# DB.net
KiCad netlist of a schematic drawn in Altium Designer
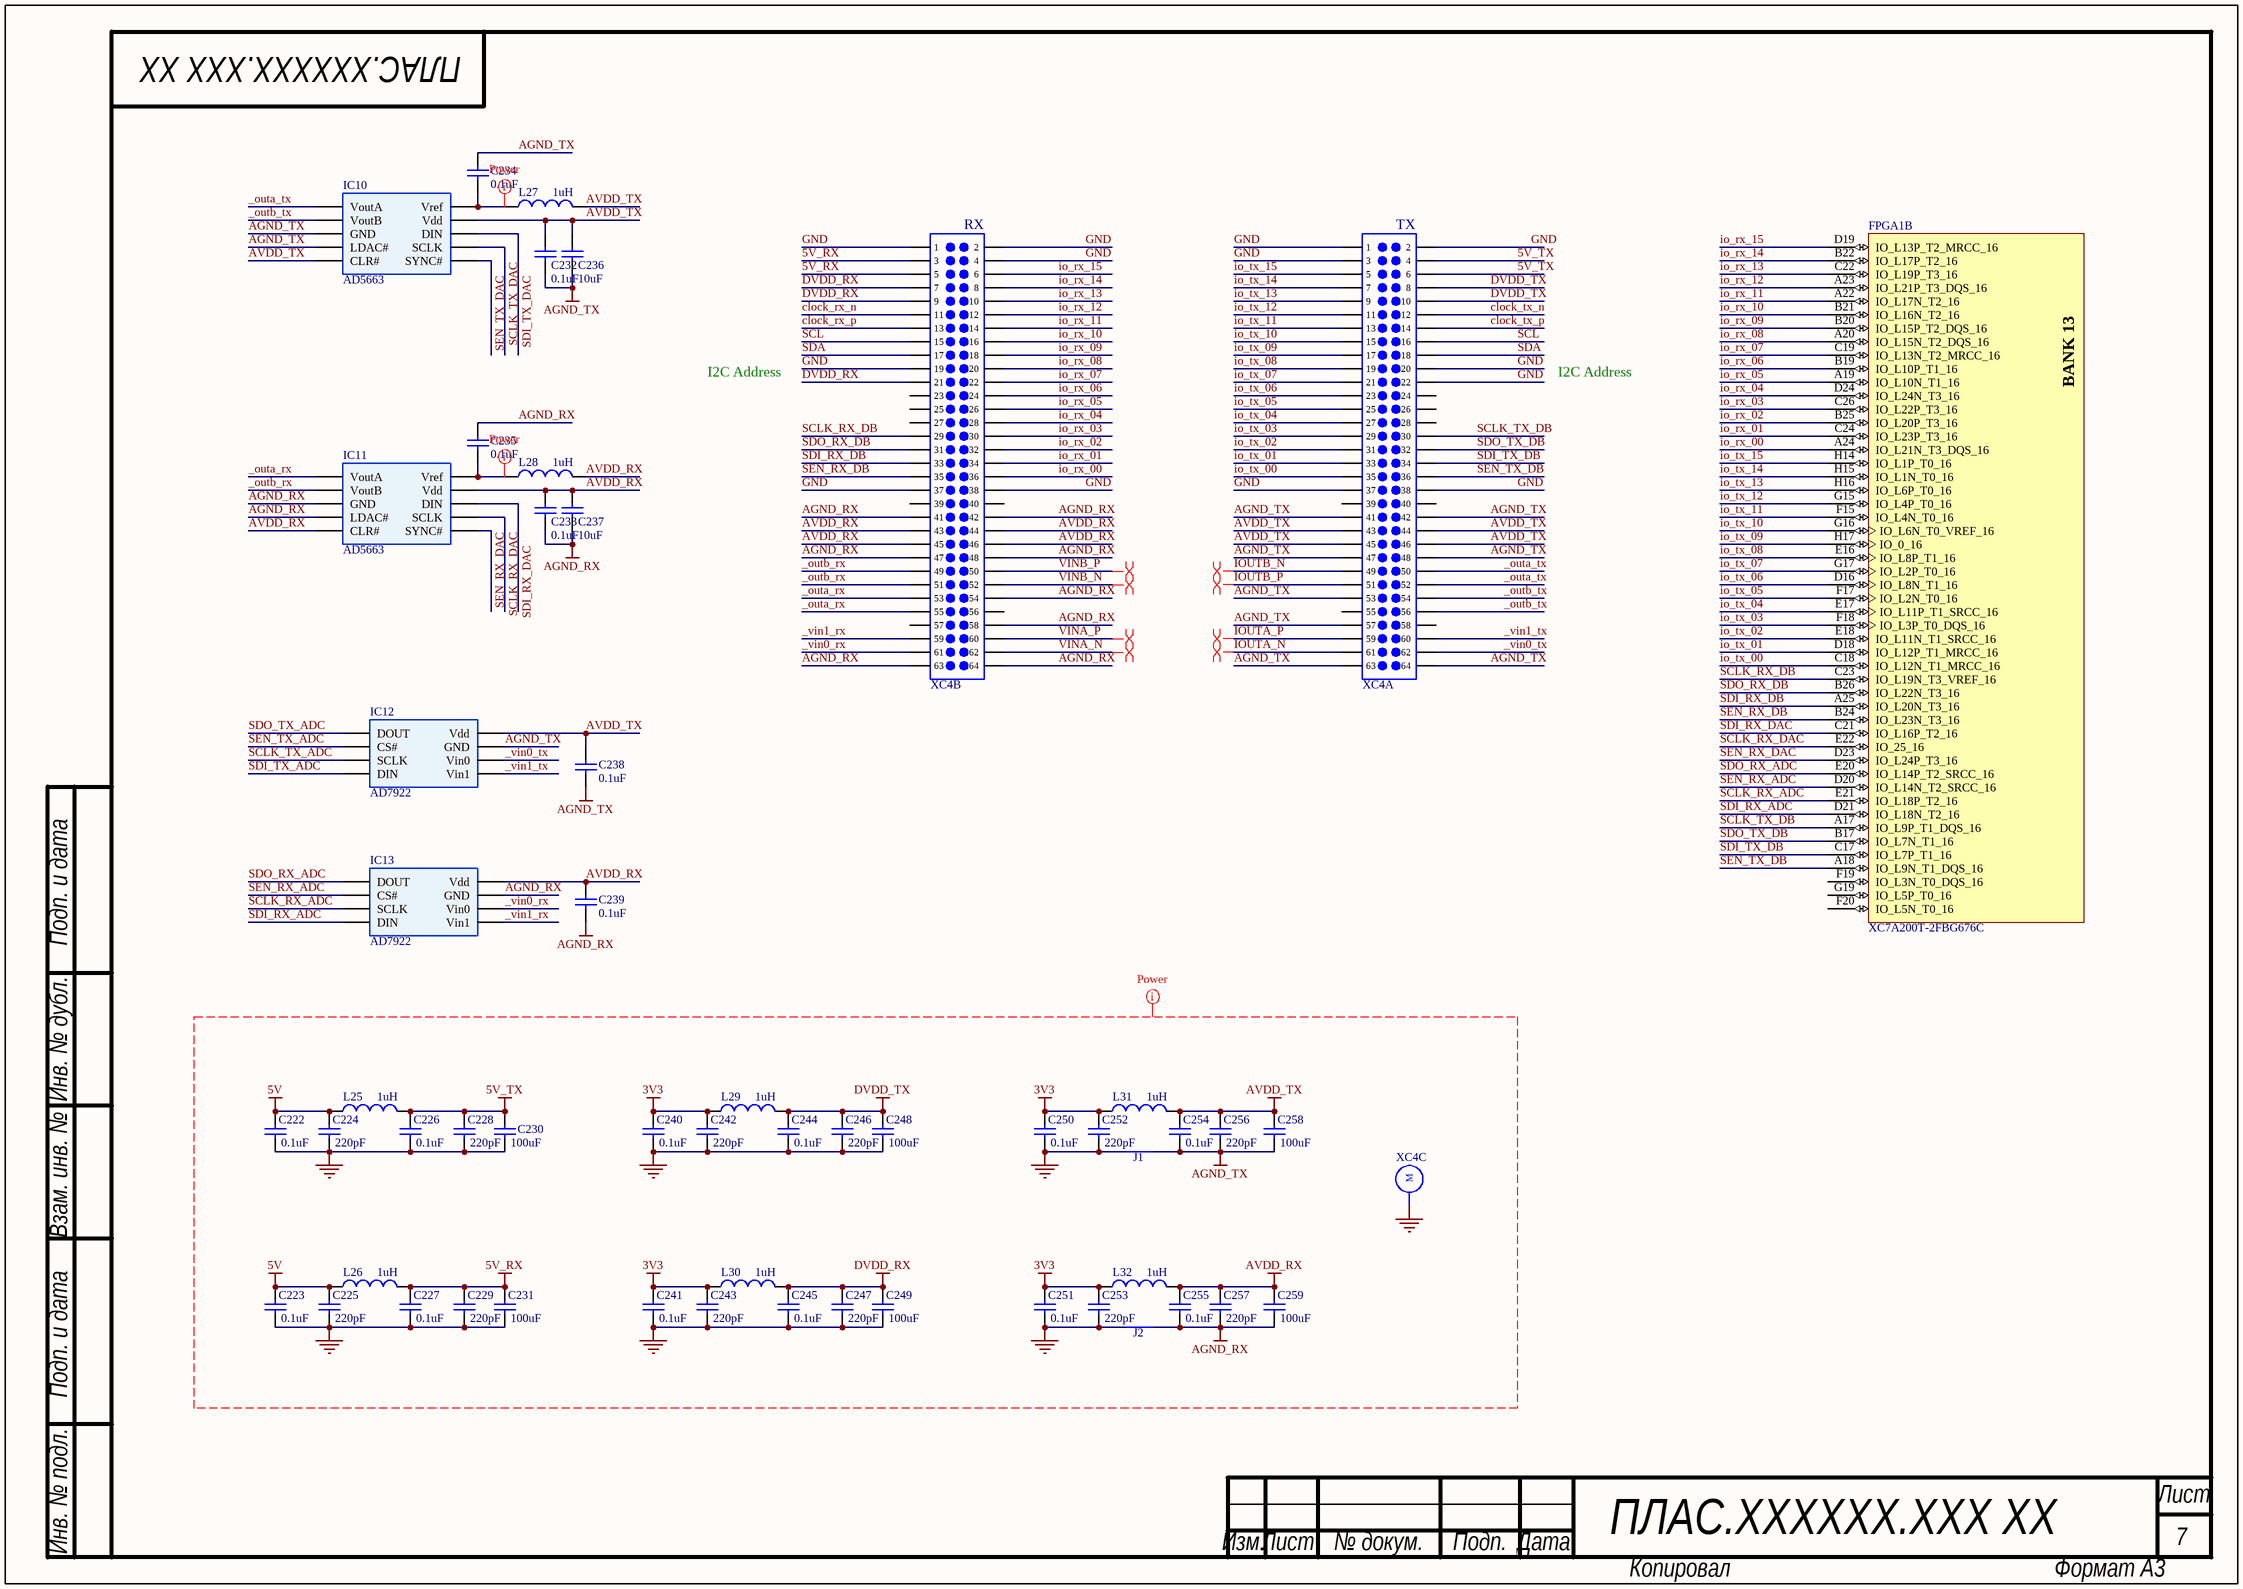
[diagram p0: DB.SchDoc]

(export (version "E")
  (design (tool "Eeschema 10.0.6"))
  (components
    (comp (ref "C222")
      (value "0.1uF")
      (footprint "C0603")
      (description "Cer Cap Small")
      (fields (field (name "MANUFACTURER") "Murata") (field (name "VOLTAGE") "16V"))
      (libsource (lib "USRP2_Clone") (part "Cer Cap"))
    )
    (comp (ref "C223")
      (value "0.1uF")
      (footprint "C0603")
      (description "Cer Cap Small")
      (fields (field (name "MANUFACTURER") "Murata") (field (name "VOLTAGE") "16V"))
      (libsource (lib "USRP2_Clone") (part "Cer Cap"))
    )
    (comp (ref "C224")
      (value "220pF")
      (footprint "C0603")
      (description "Cer Cap Small")
      (fields (field (name "MANUFACTURER") "Murata") (field (name "VOLTAGE") "16V"))
      (libsource (lib "USRP2_Clone") (part "Cer Cap"))
    )
    (comp (ref "C225")
      (value "220pF")
      (footprint "C0603")
      (description "Cer Cap Small")
      (fields (field (name "MANUFACTURER") "Murata") (field (name "VOLTAGE") "16V"))
      (libsource (lib "USRP2_Clone") (part "Cer Cap"))
    )
    (comp (ref "C226")
      (value "0.1uF")
      (footprint "C0603")
      (description "Cer Cap Small")
      (fields (field (name "MANUFACTURER") "Murata") (field (name "VOLTAGE") "16V"))
      (libsource (lib "USRP2_Clone") (part "Cer Cap"))
    )
    (comp (ref "C227")
      (value "0.1uF")
      (footprint "C0603")
      (description "Cer Cap Small")
      (fields (field (name "MANUFACTURER") "Murata") (field (name "VOLTAGE") "16V"))
      (libsource (lib "USRP2_Clone") (part "Cer Cap"))
    )
    (comp (ref "C228")
      (value "220pF")
      (footprint "C0603")
      (description "Cer Cap Small")
      (fields (field (name "MANUFACTURER") "Murata") (field (name "VOLTAGE") "16V"))
      (libsource (lib "USRP2_Clone") (part "Cer Cap"))
    )
    (comp (ref "C229")
      (value "220pF")
      (footprint "C0603")
      (description "Cer Cap Small")
      (fields (field (name "MANUFACTURER") "Murata") (field (name "VOLTAGE") "16V"))
      (libsource (lib "USRP2_Clone") (part "Cer Cap"))
    )
    (comp (ref "C230")
      (value "100uF")
      (footprint "C1210")
      (description "Cer Cap Large")
      (fields (field (name "MANUFACTURER") "Murata") (field (name "TOLERANCE") "20%"))
      (libsource (lib "USRP2_Clone") (part "Cap uF"))
    )
    (comp (ref "C231")
      (value "100uF")
      (footprint "C1210")
      (description "Cer Cap Large")
      (fields (field (name "MANUFACTURER") "Murata") (field (name "TOLERANCE") "20%"))
      (libsource (lib "USRP2_Clone") (part "Cap uF"))
    )
    (comp (ref "C232")
      (value "0.1uF")
      (footprint "C0603")
      (description "Cer Cap Small")
      (fields (field (name "MANUFACTURER") "Murata") (field (name "VOLTAGE") "16V"))
      (libsource (lib "USRP2_Clone") (part "Cer Cap"))
    )
    (comp (ref "C233")
      (value "0.1uF")
      (footprint "C0603")
      (description "Cer Cap Small")
      (fields (field (name "MANUFACTURER") "Murata") (field (name "VOLTAGE") "16V"))
      (libsource (lib "USRP2_Clone") (part "Cer Cap"))
    )
    (comp (ref "C234")
      (value "0.1uF")
      (footprint "C0603")
      (description "Cer Cap Small")
      (fields (field (name "MANUFACTURER") "Murata") (field (name "VOLTAGE") "16V"))
      (libsource (lib "USRP2_Clone") (part "Cer Cap"))
    )
    (comp (ref "C235")
      (value "0.1uF")
      (footprint "C0603")
      (description "Cer Cap Small")
      (fields (field (name "MANUFACTURER") "Murata") (field (name "VOLTAGE") "16V"))
      (libsource (lib "USRP2_Clone") (part "Cer Cap"))
    )
    (comp (ref "C236")
      (value "10uF")
      (footprint "C0603")
      (description "Cer Cap Small")
      (fields (field (name "MANUFACTURER") "Murata") (field (name "VOLTAGE") "6.3V"))
      (libsource (lib "USRP2_Clone") (part "Cer Cap"))
    )
    (comp (ref "C237")
      (value "10uF")
      (footprint "C0603")
      (description "Cer Cap Small")
      (fields (field (name "MANUFACTURER") "Murata") (field (name "VOLTAGE") "6.3V"))
      (libsource (lib "USRP2_Clone") (part "Cer Cap"))
    )
    (comp (ref "C238")
      (value "0.1uF")
      (footprint "C0603")
      (description "Cer Cap Small")
      (fields (field (name "MANUFACTURER") "Murata") (field (name "VOLTAGE") "16V"))
      (libsource (lib "") (part "Cer Cap_1"))
    )
    (comp (ref "C239")
      (value "0.1uF")
      (footprint "C0603")
      (description "Cer Cap Small")
      (fields (field (name "MANUFACTURER") "Murata") (field (name "VOLTAGE") "16V"))
      (libsource (lib "USRP2_Clone") (part "Cer Cap"))
    )
    (comp (ref "C240")
      (value "0.1uF")
      (footprint "C0603")
      (description "Cer Cap Small")
      (fields (field (name "MANUFACTURER") "Murata") (field (name "VOLTAGE") "16V"))
      (libsource (lib "USRP2_Clone") (part "Cer Cap"))
    )
    (comp (ref "C241")
      (value "0.1uF")
      (footprint "C0603")
      (description "Cer Cap Small")
      (fields (field (name "MANUFACTURER") "Murata") (field (name "VOLTAGE") "16V"))
      (libsource (lib "USRP2_Clone") (part "Cer Cap"))
    )
    (comp (ref "C242")
      (value "220pF")
      (footprint "C0603")
      (description "Cer Cap Small")
      (fields (field (name "MANUFACTURER") "Murata") (field (name "VOLTAGE") "16V"))
      (libsource (lib "USRP2_Clone") (part "Cer Cap"))
    )
    (comp (ref "C243")
      (value "220pF")
      (footprint "C0603")
      (description "Cer Cap Small")
      (fields (field (name "MANUFACTURER") "Murata") (field (name "VOLTAGE") "16V"))
      (libsource (lib "USRP2_Clone") (part "Cer Cap"))
    )
    (comp (ref "C244")
      (value "0.1uF")
      (footprint "C0603")
      (description "Cer Cap Small")
      (fields (field (name "MANUFACTURER") "Murata") (field (name "VOLTAGE") "16V"))
      (libsource (lib "USRP2_Clone") (part "Cer Cap"))
    )
    (comp (ref "C245")
      (value "0.1uF")
      (footprint "C0603")
      (description "Cer Cap Small")
      (fields (field (name "MANUFACTURER") "Murata") (field (name "VOLTAGE") "16V"))
      (libsource (lib "USRP2_Clone") (part "Cer Cap"))
    )
    (comp (ref "C246")
      (value "220pF")
      (footprint "C0603")
      (description "Cer Cap Small")
      (fields (field (name "MANUFACTURER") "Murata") (field (name "VOLTAGE") "16V"))
      (libsource (lib "USRP2_Clone") (part "Cer Cap"))
    )
    (comp (ref "C247")
      (value "220pF")
      (footprint "C0603")
      (description "Cer Cap Small")
      (fields (field (name "MANUFACTURER") "Murata") (field (name "VOLTAGE") "16V"))
      (libsource (lib "USRP2_Clone") (part "Cer Cap"))
    )
    (comp (ref "C248")
      (value "100uF")
      (footprint "C1210")
      (description "Cer Cap Large")
      (fields (field (name "MANUFACTURER") "Murata") (field (name "TOLERANCE") "20%"))
      (libsource (lib "USRP2_Clone") (part "Cap uF"))
    )
    (comp (ref "C249")
      (value "100uF")
      (footprint "C1210")
      (description "Cer Cap Large")
      (fields (field (name "MANUFACTURER") "Murata") (field (name "TOLERANCE") "20%"))
      (libsource (lib "USRP2_Clone") (part "Cap uF"))
    )
    (comp (ref "C250")
      (value "0.1uF")
      (footprint "C0603")
      (description "Cer Cap Small")
      (fields (field (name "MANUFACTURER") "Murata") (field (name "VOLTAGE") "16V"))
      (libsource (lib "USRP2_Clone") (part "Cer Cap"))
    )
    (comp (ref "C251")
      (value "0.1uF")
      (footprint "C0603")
      (description "Cer Cap Small")
      (fields (field (name "MANUFACTURER") "Murata") (field (name "VOLTAGE") "16V"))
      (libsource (lib "USRP2_Clone") (part "Cer Cap"))
    )
    (comp (ref "C252")
      (value "220pF")
      (footprint "C0603")
      (description "Cer Cap Small")
      (fields (field (name "MANUFACTURER") "Murata") (field (name "VOLTAGE") "16V"))
      (libsource (lib "USRP2_Clone") (part "Cer Cap"))
    )
    (comp (ref "C253")
      (value "220pF")
      (footprint "C0603")
      (description "Cer Cap Small")
      (fields (field (name "MANUFACTURER") "Murata") (field (name "VOLTAGE") "16V"))
      (libsource (lib "USRP2_Clone") (part "Cer Cap"))
    )
    (comp (ref "C254")
      (value "0.1uF")
      (footprint "C0603")
      (description "Cer Cap Small")
      (fields (field (name "MANUFACTURER") "Murata") (field (name "VOLTAGE") "16V"))
      (libsource (lib "USRP2_Clone") (part "Cer Cap"))
    )
    (comp (ref "C255")
      (value "0.1uF")
      (footprint "C0603")
      (description "Cer Cap Small")
      (fields (field (name "MANUFACTURER") "Murata") (field (name "VOLTAGE") "16V"))
      (libsource (lib "USRP2_Clone") (part "Cer Cap"))
    )
    (comp (ref "C256")
      (value "220pF")
      (footprint "C0603")
      (description "Cer Cap Small")
      (fields (field (name "MANUFACTURER") "Murata") (field (name "VOLTAGE") "16V"))
      (libsource (lib "USRP2_Clone") (part "Cer Cap"))
    )
    (comp (ref "C257")
      (value "220pF")
      (footprint "C0603")
      (description "Cer Cap Small")
      (fields (field (name "MANUFACTURER") "Murata") (field (name "VOLTAGE") "16V"))
      (libsource (lib "USRP2_Clone") (part "Cer Cap"))
    )
    (comp (ref "C258")
      (value "100uF")
      (footprint "C1210")
      (description "Cer Cap Large")
      (fields (field (name "MANUFACTURER") "Murata") (field (name "TOLERANCE") "20%"))
      (libsource (lib "USRP2_Clone") (part "Cap uF"))
    )
    (comp (ref "C259")
      (value "100uF")
      (footprint "C1210")
      (description "Cer Cap Large")
      (fields (field (name "MANUFACTURER") "Murata") (field (name "TOLERANCE") "20%"))
      (libsource (lib "USRP2_Clone") (part "Cap uF"))
    )
    (comp (ref "FPGA1")
      (value "XC7A200T-2FBG676C")
      (footprint "FGG676")
      (description "Artix-7 FPGA, 400 User I/Os, 8 GTP, 676-Ball BGA, Speed Grade 2, Commercial Grade, Pb-Free")
      (fields (field (name "GENERIC PART NUMBER") "XC7A200T") (field (name "MANUFACTURER") "Xilinx"))
      (libsource (lib "USRP2_Clone") (part "XC7A200T-2FBG676C"))
    )
    (comp (ref "IC10")
      (value "AD5663")
      (footprint "MSOP-10")
      (description "Dual 12-/14-/16-Bit nanoDAC")
      (fields (field (name "VOLTAGE") "2.7 V to 5.5 V") (field (name "MANUFACTURER") "Analog Device"))
      (libsource (lib "USRP2_Clone") (part "AD56x3R"))
    )
    (comp (ref "IC11")
      (value "AD5663")
      (footprint "MSOP-10")
      (description "Dual 12-/14-/16-Bit nanoDAC")
      (fields (field (name "VOLTAGE") "2.7 V to 5.5 V") (field (name "MANUFACTURER") "Analog Device"))
      (libsource (lib "USRP2_Clone") (part "AD56x3R"))
    )
    (comp (ref "IC12")
      (value "AD7922")
      (footprint "MSOP-8")
      (description "1 MSPS, 10-/12-Bit ADC")
      (fields (field (name "VOLTAGE") "2.35 V to 5.25 V") (field (name "MANUFACTURER") "Analog Device"))
      (libsource (lib "USRP2_Clone") (part "AD79x2"))
    )
    (comp (ref "IC13")
      (value "AD7922")
      (footprint "MSOP-8")
      (description "1 MSPS, 10-/12-Bit ADC")
      (fields (field (name "VOLTAGE") "2.35 V to 5.25 V") (field (name "MANUFACTURER") "Analog Device"))
      (libsource (lib "USRP2_Clone") (part "AD79x2"))
    )
    (comp (ref "J1")
      (value "JMP")
      (footprint "JUMPER")
      (description "PGND & AGND Connect")
      (libsource (lib "USRP2_Clone") (part "JMP"))
    )
    (comp (ref "J2")
      (value "JMP")
      (footprint "JUMPER")
      (description "PGND & AGND Connect")
      (libsource (lib "USRP2_Clone") (part "JMP"))
    )
    (comp (ref "L25")
      (value "1uH")
      (footprint "L1210_Murata LQH")
      (description "Inductor_Power_Lines")
      (fields (field (name "TOLERANCE") "5%") (field (name "MANUFACTURER") "Murata"))
      (libsource (lib "USRP2_Clone") (part "Inductor_LF"))
    )
    (comp (ref "L26")
      (value "1uH")
      (footprint "L1210_Murata LQH")
      (description "Inductor_Power_Lines")
      (fields (field (name "TOLERANCE") "5%") (field (name "MANUFACTURER") "Murata"))
      (libsource (lib "") (part "Inductor_LF_1"))
    )
    (comp (ref "L27")
      (value "1uH")
      (footprint "L1206_Murata")
      (description "Inductor_Power_Lines")
      (fields (field (name "TOLERANCE") "5%") (field (name "MANUFACTURER") "Murata"))
      (libsource (lib "") (part "Inductor_LF_1"))
    )
    (comp (ref "L28")
      (value "1uH")
      (footprint "L1206_Murata")
      (description "Inductor_Power_Lines")
      (fields (field (name "TOLERANCE") "5%") (field (name "MANUFACTURER") "Murata"))
      (libsource (lib "") (part "Inductor_LF_1"))
    )
    (comp (ref "L29")
      (value "1uH")
      (footprint "L1210_Murata LQH")
      (description "Inductor_Power_Lines")
      (fields (field (name "TOLERANCE") "5%") (field (name "MANUFACTURER") "Murata"))
      (libsource (lib "") (part "Inductor_LF_1"))
    )
    (comp (ref "L30")
      (value "1uH")
      (footprint "L1210_Murata LQH")
      (description "Inductor_Power_Lines")
      (fields (field (name "TOLERANCE") "5%") (field (name "MANUFACTURER") "Murata"))
      (libsource (lib "") (part "Inductor_LF_1"))
    )
    (comp (ref "L31")
      (value "1uH")
      (footprint "L1210_Murata LQH")
      (description "Inductor_Power_Lines")
      (fields (field (name "TOLERANCE") "5%") (field (name "MANUFACTURER") "Murata"))
      (libsource (lib "USRP2_Clone") (part "Inductor_LF"))
    )
    (comp (ref "L32")
      (value "1uH")
      (footprint "L1210_Murata LQH")
      (description "Inductor_Power_Lines")
      (fields (field (name "TOLERANCE") "5%") (field (name "MANUFACTURER") "Murata"))
      (libsource (lib "USRP2_Clone") (part "Inductor_LF"))
    )
    (comp (ref "XC4")
      (value "64-pin Male Mezzanine")
      (footprint "RFX")
      (description "RFX")
      (libsource (lib "USRP2_Clone") (part "RFX"))
    )
  )
  (nets
    (net (code "1") (name "/IOUTA_N") (class "Default")
      (node (ref "XC4") (pin "61") (pinfunction "61_61") (pintype "passive"))
    )
    (net (code "2") (name "/IOUTA_P") (class "Default")
      (node (ref "XC4") (pin "59") (pinfunction "59_59") (pintype "passive"))
    )
    (net (code "3") (name "/IOUTB_N") (class "Default")
      (node (ref "XC4") (pin "49") (pinfunction "49_49") (pintype "passive"))
    )
    (net (code "4") (name "/IOUTB_P") (class "Default")
      (node (ref "XC4") (pin "51") (pinfunction "51_51") (pintype "passive"))
    )
    (net (code "5") (name "/SCL") (class "Default")
      (node (ref "XC4") (pin "16") (pinfunction "16_16") (pintype "passive"))
      (node (ref "XC4") (pin "79") (pinfunction "15_79") (pintype "passive"))
    )
    (net (code "6") (name "/SCLK_RX_ADC") (class "Default")
      (node (ref "FPGA1") (pin "E21") (pinfunction "IO_L18P_T2_16_E21") (pintype "bidirectional"))
      (node (ref "IC13") (pin "3") (pinfunction "SCLK_3") (pintype "passive"))
    )
    (net (code "7") (name "/SCLK_RX_DAC") (class "Default")
      (node (ref "FPGA1") (pin "E22") (pinfunction "IO_25_16_E22") (pintype "bidirectional"))
      (node (ref "IC11") (pin "7") (pinfunction "SCLK_7") (pintype "passive"))
    )
    (net (code "8") (name "/SCLK_RX_DB") (class "Default")
      (node (ref "FPGA1") (pin "C23") (pinfunction "IO_L19N_T3_VREF_16_C23") (pintype "bidirectional"))
      (node (ref "XC4") (pin "93") (pinfunction "29_93") (pintype "passive"))
    )
    (net (code "9") (name "/SCLK_TX_ADC") (class "Default")
      (node (ref "IC12") (pin "3") (pinfunction "SCLK_3") (pintype "passive"))
    )
    (net (code "10") (name "/SCLK_TX_DAC") (class "Default")
      (node (ref "IC10") (pin "7") (pinfunction "SCLK_7") (pintype "passive"))
    )
    (net (code "11") (name "/SCLK_TX_DB") (class "Default")
      (node (ref "FPGA1") (pin "A17") (pinfunction "IO_L9P_T1_DQS_16_A17") (pintype "bidirectional"))
      (node (ref "XC4") (pin "30") (pinfunction "30_30") (pintype "passive"))
    )
    (net (code "12") (name "/SDA") (class "Default")
      (node (ref "XC4") (pin "18") (pinfunction "18_18") (pintype "passive"))
      (node (ref "XC4") (pin "81") (pinfunction "17_81") (pintype "passive"))
    )
    (net (code "13") (name "/SDI_RX_ADC") (class "Default")
      (node (ref "FPGA1") (pin "D21") (pinfunction "IO_L18N_T2_16_D21") (pintype "bidirectional"))
      (node (ref "IC13") (pin "4") (pinfunction "DIN_4") (pintype "passive"))
    )
    (net (code "14") (name "/SDI_RX_DAC") (class "Default")
      (node (ref "FPGA1") (pin "C21") (pinfunction "IO_L16P_T2_16_C21") (pintype "bidirectional"))
      (node (ref "IC11") (pin "8") (pinfunction "DIN_8") (pintype "passive"))
    )
    (net (code "15") (name "/SDI_RX_DB") (class "Default")
      (node (ref "FPGA1") (pin "A25") (pinfunction "IO_L20N_T3_16_A25") (pintype "bidirectional"))
      (node (ref "XC4") (pin "97") (pinfunction "33_97") (pintype "passive"))
    )
    (net (code "16") (name "/SDI_TX_ADC") (class "Default")
      (node (ref "IC12") (pin "4") (pinfunction "DIN_4") (pintype "passive"))
    )
    (net (code "17") (name "/SDI_TX_DAC") (class "Default")
      (node (ref "IC10") (pin "8") (pinfunction "DIN_8") (pintype "passive"))
    )
    (net (code "18") (name "/SDI_TX_DB") (class "Default")
      (node (ref "FPGA1") (pin "C17") (pinfunction "IO_L7P_T1_16_C17") (pintype "bidirectional"))
      (node (ref "XC4") (pin "34") (pinfunction "34_34") (pintype "passive"))
    )
    (net (code "19") (name "/SDO_RX_ADC") (class "Default")
      (node (ref "FPGA1") (pin "E20") (pinfunction "IO_L14P_T2_SRCC_16_E20") (pintype "bidirectional"))
      (node (ref "IC13") (pin "1") (pinfunction "DOUT_1") (pintype "passive"))
    )
    (net (code "20") (name "/SDO_RX_DB") (class "Default")
      (node (ref "FPGA1") (pin "B26") (pinfunction "IO_L22N_T3_16_B26") (pintype "bidirectional"))
      (node (ref "XC4") (pin "95") (pinfunction "31_95") (pintype "passive"))
    )
    (net (code "21") (name "/SDO_TX_ADC") (class "Default")
      (node (ref "IC12") (pin "1") (pinfunction "DOUT_1") (pintype "passive"))
    )
    (net (code "22") (name "/SDO_TX_DB") (class "Default")
      (node (ref "FPGA1") (pin "B17") (pinfunction "IO_L7N_T1_16_B17") (pintype "bidirectional"))
      (node (ref "XC4") (pin "32") (pinfunction "32_32") (pintype "passive"))
    )
    (net (code "23") (name "/SEN_RX_ADC") (class "Default")
      (node (ref "FPGA1") (pin "D20") (pinfunction "IO_L14N_T2_SRCC_16_D20") (pintype "bidirectional"))
      (node (ref "IC13") (pin "2") (pinfunction "CS#_2") (pintype "passive"))
    )
    (net (code "24") (name "/SEN_RX_DAC") (class "Default")
      (node (ref "FPGA1") (pin "D23") (pinfunction "IO_L24P_T3_16_D23") (pintype "bidirectional"))
      (node (ref "IC11") (pin "6") (pinfunction "SYNC#_6") (pintype "passive"))
    )
    (net (code "25") (name "/SEN_RX_DB") (class "Default")
      (node (ref "FPGA1") (pin "B24") (pinfunction "IO_L23N_T3_16_B24") (pintype "bidirectional"))
      (node (ref "XC4") (pin "99") (pinfunction "35_99") (pintype "passive"))
    )
    (net (code "26") (name "/SEN_TX_ADC") (class "Default")
      (node (ref "IC12") (pin "2") (pinfunction "CS#_2") (pintype "passive"))
    )
    (net (code "27") (name "/SEN_TX_DAC") (class "Default")
      (node (ref "IC10") (pin "6") (pinfunction "SYNC#_6") (pintype "passive"))
    )
    (net (code "28") (name "/SEN_TX_DB") (class "Default")
      (node (ref "FPGA1") (pin "A18") (pinfunction "IO_L9N_T1_DQS_16_A18") (pintype "bidirectional"))
      (node (ref "XC4") (pin "36") (pinfunction "36_36") (pintype "passive"))
    )
    (net (code "29") (name "/VINA_N") (class "Default")
      (node (ref "XC4") (pin "126") (pinfunction "62_126") (pintype "passive"))
    )
    (net (code "30") (name "/VINA_P") (class "Default")
      (node (ref "XC4") (pin "124") (pinfunction "60_124") (pintype "passive"))
    )
    (net (code "31") (name "/VINB_N") (class "Default")
      (node (ref "XC4") (pin "116") (pinfunction "52_116") (pintype "passive"))
    )
    (net (code "32") (name "/VINB_P") (class "Default")
      (node (ref "XC4") (pin "114") (pinfunction "50_114") (pintype "passive"))
    )
    (net (code "33") (name "/_outa_rx") (class "Default")
      (node (ref "IC11") (pin "1") (pinfunction "VoutA_1") (pintype "passive"))
      (node (ref "XC4") (pin "117") (pinfunction "53_117") (pintype "passive"))
      (node (ref "XC4") (pin "119") (pinfunction "55_119") (pintype "passive"))
    )
    (net (code "34") (name "/_outa_tx") (class "Default")
      (node (ref "IC10") (pin "1") (pinfunction "VoutA_1") (pintype "passive"))
      (node (ref "XC4") (pin "50") (pinfunction "50_50") (pintype "passive"))
      (node (ref "XC4") (pin "52") (pinfunction "52_52") (pintype "passive"))
    )
    (net (code "35") (name "/_outb_rx") (class "Default")
      (node (ref "IC11") (pin "2") (pinfunction "VoutB_2") (pintype "passive"))
      (node (ref "XC4") (pin "113") (pinfunction "49_113") (pintype "passive"))
      (node (ref "XC4") (pin "115") (pinfunction "51_115") (pintype "passive"))
    )
    (net (code "36") (name "/_outb_tx") (class "Default")
      (node (ref "IC10") (pin "2") (pinfunction "VoutB_2") (pintype "passive"))
      (node (ref "XC4") (pin "54") (pinfunction "54_54") (pintype "passive"))
      (node (ref "XC4") (pin "56") (pinfunction "56_56") (pintype "passive"))
    )
    (net (code "37") (name "/_vin0_rx") (class "Default")
      (node (ref "IC13") (pin "6") (pinfunction "Vin0_6") (pintype "passive"))
      (node (ref "XC4") (pin "125") (pinfunction "61_125") (pintype "passive"))
    )
    (net (code "38") (name "/_vin0_tx") (class "Default")
      (node (ref "IC12") (pin "6") (pinfunction "Vin0_6") (pintype "passive"))
      (node (ref "XC4") (pin "62") (pinfunction "62_62") (pintype "passive"))
    )
    (net (code "39") (name "/_vin1_rx") (class "Default")
      (node (ref "IC13") (pin "5") (pinfunction "Vin1_5") (pintype "passive"))
      (node (ref "XC4") (pin "123") (pinfunction "59_123") (pintype "passive"))
    )
    (net (code "40") (name "/_vin1_tx") (class "Default")
      (node (ref "IC12") (pin "5") (pinfunction "Vin1_5") (pintype "passive"))
      (node (ref "XC4") (pin "60") (pinfunction "60_60") (pintype "passive"))
    )
    (net (code "41") (name "/clock_rx_n") (class "Default")
      (node (ref "XC4") (pin "75") (pinfunction "11_75") (pintype "passive"))
    )
    (net (code "42") (name "/clock_rx_p") (class "Default")
      (node (ref "XC4") (pin "77") (pinfunction "13_77") (pintype "passive"))
    )
    (net (code "43") (name "/clock_tx_n") (class "Default")
      (node (ref "XC4") (pin "12") (pinfunction "12_12") (pintype "passive"))
    )
    (net (code "44") (name "/clock_tx_p") (class "Default")
      (node (ref "XC4") (pin "14") (pinfunction "14_14") (pintype "passive"))
    )
    (net (code "45") (name "/io_rx_00") (class "Default")
      (node (ref "FPGA1") (pin "A24") (pinfunction "IO_L21N_T3_DQS_16_A24") (pintype "bidirectional"))
      (node (ref "XC4") (pin "100") (pinfunction "36_100") (pintype "passive"))
    )
    (net (code "46") (name "/io_rx_01") (class "Default")
      (node (ref "FPGA1") (pin "C24") (pinfunction "IO_L23P_T3_16_C24") (pintype "bidirectional"))
      (node (ref "XC4") (pin "98") (pinfunction "34_98") (pintype "passive"))
    )
    (net (code "47") (name "/io_rx_02") (class "Default")
      (node (ref "FPGA1") (pin "B25") (pinfunction "IO_L20P_T3_16_B25") (pintype "bidirectional"))
      (node (ref "XC4") (pin "96") (pinfunction "32_96") (pintype "passive"))
    )
    (net (code "48") (name "/io_rx_03") (class "Default")
      (node (ref "FPGA1") (pin "C26") (pinfunction "IO_L22P_T3_16_C26") (pintype "bidirectional"))
      (node (ref "XC4") (pin "94") (pinfunction "30_94") (pintype "passive"))
    )
    (net (code "49") (name "/io_rx_04") (class "Default")
      (node (ref "FPGA1") (pin "D24") (pinfunction "IO_L24N_T3_16_D24") (pintype "bidirectional"))
      (node (ref "XC4") (pin "92") (pinfunction "28_92") (pintype "passive"))
    )
    (net (code "50") (name "/io_rx_05") (class "Default")
      (node (ref "FPGA1") (pin "A19") (pinfunction "IO_L10N_T1_16_A19") (pintype "bidirectional"))
      (node (ref "XC4") (pin "90") (pinfunction "26_90") (pintype "passive"))
    )
    (net (code "51") (name "/io_rx_06") (class "Default")
      (node (ref "FPGA1") (pin "B19") (pinfunction "IO_L10P_T1_16_B19") (pintype "bidirectional"))
      (node (ref "XC4") (pin "88") (pinfunction "24_88") (pintype "passive"))
    )
    (net (code "52") (name "/io_rx_07") (class "Default")
      (node (ref "FPGA1") (pin "C19") (pinfunction "IO_L13N_T2_MRCC_16_C19") (pintype "bidirectional"))
      (node (ref "XC4") (pin "86") (pinfunction "22_86") (pintype "passive"))
    )
    (net (code "53") (name "/io_rx_08") (class "Default")
      (node (ref "FPGA1") (pin "A20") (pinfunction "IO_L15N_T2_DQS_16_A20") (pintype "bidirectional"))
      (node (ref "XC4") (pin "84") (pinfunction "20_84") (pintype "passive"))
    )
    (net (code "54") (name "/io_rx_09") (class "Default")
      (node (ref "FPGA1") (pin "B20") (pinfunction "IO_L15P_T2_DQS_16_B20") (pintype "bidirectional"))
      (node (ref "XC4") (pin "82") (pinfunction "18_82") (pintype "passive"))
    )
    (net (code "55") (name "/io_rx_10") (class "Default")
      (node (ref "FPGA1") (pin "B21") (pinfunction "IO_L16N_T2_16_B21") (pintype "bidirectional"))
      (node (ref "XC4") (pin "80") (pinfunction "16_80") (pintype "passive"))
    )
    (net (code "56") (name "/io_rx_11") (class "Default")
      (node (ref "FPGA1") (pin "A22") (pinfunction "IO_L17N_T2_16_A22") (pintype "bidirectional"))
      (node (ref "XC4") (pin "78") (pinfunction "14_78") (pintype "passive"))
    )
    (net (code "57") (name "/io_rx_12") (class "Default")
      (node (ref "FPGA1") (pin "A23") (pinfunction "IO_L21P_T3_DQS_16_A23") (pintype "bidirectional"))
      (node (ref "XC4") (pin "76") (pinfunction "12_76") (pintype "passive"))
    )
    (net (code "58") (name "/io_rx_13") (class "Default")
      (node (ref "FPGA1") (pin "C22") (pinfunction "IO_L19P_T3_16_C22") (pintype "bidirectional"))
      (node (ref "XC4") (pin "74") (pinfunction "10_74") (pintype "passive"))
    )
    (net (code "59") (name "/io_rx_14") (class "Default")
      (node (ref "FPGA1") (pin "B22") (pinfunction "IO_L17P_T2_16_B22") (pintype "bidirectional"))
      (node (ref "XC4") (pin "72") (pinfunction "8_72") (pintype "passive"))
    )
    (net (code "60") (name "/io_rx_15") (class "Default")
      (node (ref "FPGA1") (pin "D19") (pinfunction "IO_L13P_T2_MRCC_16_D19") (pintype "bidirectional"))
      (node (ref "XC4") (pin "70") (pinfunction "6_70") (pintype "passive"))
    )
    (net (code "61") (name "/io_tx_00") (class "Default")
      (node (ref "FPGA1") (pin "C18") (pinfunction "IO_L12N_T1_MRCC_16_C18") (pintype "bidirectional"))
      (node (ref "XC4") (pin "35") (pinfunction "35_35") (pintype "passive"))
    )
    (net (code "62") (name "/io_tx_01") (class "Default")
      (node (ref "FPGA1") (pin "D18") (pinfunction "IO_L12P_T1_MRCC_16_D18") (pintype "bidirectional"))
      (node (ref "XC4") (pin "33") (pinfunction "33_33") (pintype "passive"))
    )
    (net (code "63") (name "/io_tx_02") (class "Default")
      (node (ref "FPGA1") (pin "E18") (pinfunction "IO_L11N_T1_SRCC_16_E18") (pintype "bidirectional"))
      (node (ref "XC4") (pin "31") (pinfunction "31_31") (pintype "passive"))
    )
    (net (code "64") (name "/io_tx_03") (class "Default")
      (node (ref "FPGA1") (pin "F18") (pinfunction "IO_L3P_T0_DQS_16_F18") (pintype "bidirectional"))
      (node (ref "XC4") (pin "29") (pinfunction "29_29") (pintype "passive"))
    )
    (net (code "65") (name "/io_tx_04") (class "Default")
      (node (ref "FPGA1") (pin "E17") (pinfunction "IO_L11P_T1_SRCC_16_E17") (pintype "bidirectional"))
      (node (ref "XC4") (pin "27") (pinfunction "27_27") (pintype "passive"))
    )
    (net (code "66") (name "/io_tx_05") (class "Default")
      (node (ref "FPGA1") (pin "F17") (pinfunction "IO_L2N_T0_16_F17") (pintype "bidirectional"))
      (node (ref "XC4") (pin "25") (pinfunction "25_25") (pintype "passive"))
    )
    (net (code "67") (name "/io_tx_06") (class "Default")
      (node (ref "FPGA1") (pin "D16") (pinfunction "IO_L8N_T1_16_D16") (pintype "bidirectional"))
      (node (ref "XC4") (pin "23") (pinfunction "23_23") (pintype "passive"))
    )
    (net (code "68") (name "/io_tx_07") (class "Default")
      (node (ref "FPGA1") (pin "G17") (pinfunction "IO_L2P_T0_16_G17") (pintype "bidirectional"))
      (node (ref "XC4") (pin "21") (pinfunction "21_21") (pintype "passive"))
    )
    (net (code "69") (name "/io_tx_08") (class "Default")
      (node (ref "FPGA1") (pin "E16") (pinfunction "IO_L8P_T1_16_E16") (pintype "bidirectional"))
      (node (ref "XC4") (pin "19") (pinfunction "19_19") (pintype "passive"))
    )
    (net (code "70") (name "/io_tx_09") (class "Default")
      (node (ref "FPGA1") (pin "H17") (pinfunction "IO_0_16_H17") (pintype "bidirectional"))
      (node (ref "XC4") (pin "17") (pinfunction "17_17") (pintype "passive"))
    )
    (net (code "71") (name "/io_tx_10") (class "Default")
      (node (ref "FPGA1") (pin "G16") (pinfunction "IO_L6N_T0_VREF_16_G16") (pintype "bidirectional"))
      (node (ref "XC4") (pin "15") (pinfunction "15_15") (pintype "passive"))
    )
    (net (code "72") (name "/io_tx_11") (class "Default")
      (node (ref "FPGA1") (pin "F15") (pinfunction "IO_L4N_T0_16_F15") (pintype "bidirectional"))
      (node (ref "XC4") (pin "13") (pinfunction "13_13") (pintype "passive"))
    )
    (net (code "73") (name "/io_tx_12") (class "Default")
      (node (ref "FPGA1") (pin "G15") (pinfunction "IO_L4P_T0_16_G15") (pintype "bidirectional"))
      (node (ref "XC4") (pin "11") (pinfunction "11_11") (pintype "passive"))
    )
    (net (code "74") (name "/io_tx_13") (class "Default")
      (node (ref "FPGA1") (pin "H16") (pinfunction "IO_L6P_T0_16_H16") (pintype "bidirectional"))
      (node (ref "XC4") (pin "9") (pinfunction "9_9") (pintype "passive"))
    )
    (net (code "75") (name "/io_tx_14") (class "Default")
      (node (ref "FPGA1") (pin "H15") (pinfunction "IO_L1N_T0_16_H15") (pintype "bidirectional"))
      (node (ref "XC4") (pin "7") (pinfunction "7_7") (pintype "passive"))
    )
    (net (code "76") (name "/io_tx_15") (class "Default")
      (node (ref "FPGA1") (pin "H14") (pinfunction "IO_L1P_T0_16_H14") (pintype "bidirectional"))
      (node (ref "XC4") (pin "5") (pinfunction "5_5") (pintype "passive"))
    )
    (net (code "77") (name "3V3") (class "Default")
      (node (ref "C240") (pin "1") (pinfunction "1_1") (pintype "passive"))
      (node (ref "C241") (pin "1") (pinfunction "1_1") (pintype "passive"))
      (node (ref "C242") (pin "1") (pinfunction "1_1") (pintype "passive"))
      (node (ref "C243") (pin "1") (pinfunction "1_1") (pintype "passive"))
      (node (ref "C250") (pin "1") (pinfunction "1_1") (pintype "passive"))
      (node (ref "C251") (pin "1") (pinfunction "1_1") (pintype "passive"))
      (node (ref "C252") (pin "1") (pinfunction "1_1") (pintype "passive"))
      (node (ref "C253") (pin "1") (pinfunction "1_1") (pintype "passive"))
      (node (ref "L29") (pin "2") (pinfunction "2_2") (pintype "passive"))
      (node (ref "L30") (pin "2") (pinfunction "2_2") (pintype "passive"))
      (node (ref "L31") (pin "1") (pinfunction "1_1") (pintype "passive"))
      (node (ref "L32") (pin "1") (pinfunction "1_1") (pintype "passive"))
    )
    (net (code "78") (name "5V") (class "Default")
      (node (ref "C222") (pin "1") (pinfunction "1_1") (pintype "passive"))
      (node (ref "C223") (pin "1") (pinfunction "1_1") (pintype "passive"))
      (node (ref "C224") (pin "1") (pinfunction "1_1") (pintype "passive"))
      (node (ref "C225") (pin "1") (pinfunction "1_1") (pintype "passive"))
      (node (ref "L25") (pin "1") (pinfunction "1_1") (pintype "passive"))
      (node (ref "L26") (pin "2") (pinfunction "2_2") (pintype "passive"))
    )
    (net (code "79") (name "5V_RX") (class "Default")
      (node (ref "C227") (pin "1") (pinfunction "1_1") (pintype "passive"))
      (node (ref "C229") (pin "1") (pinfunction "1_1") (pintype "passive"))
      (node (ref "C231") (pin "1") (pinfunction "1_1") (pintype "passive"))
      (node (ref "L26") (pin "1") (pinfunction "1_1") (pintype "passive"))
      (node (ref "XC4") (pin "67") (pinfunction "3_67") (pintype "passive"))
      (node (ref "XC4") (pin "69") (pinfunction "5_69") (pintype "passive"))
    )
    (net (code "80") (name "5V_TX") (class "Default")
      (node (ref "C226") (pin "1") (pinfunction "1_1") (pintype "passive"))
      (node (ref "C228") (pin "1") (pinfunction "1_1") (pintype "passive"))
      (node (ref "C230") (pin "1") (pinfunction "1_1") (pintype "passive"))
      (node (ref "L25") (pin "2") (pinfunction "2_2") (pintype "passive"))
      (node (ref "XC4") (pin "4") (pinfunction "4_4") (pintype "passive"))
      (node (ref "XC4") (pin "6") (pinfunction "6_6") (pintype "passive"))
    )
    (net (code "81") (name "AGND_RX") (class "Default")
      (node (ref "C233") (pin "2") (pinfunction "2_2") (pintype "passive"))
      (node (ref "C235") (pin "1") (pinfunction "1_1") (pintype "passive"))
      (node (ref "C237") (pin "2") (pinfunction "2_2") (pintype "passive"))
      (node (ref "C239") (pin "2") (pinfunction "2_2") (pintype "passive"))
      (node (ref "C255") (pin "2") (pinfunction "2_2") (pintype "passive"))
      (node (ref "C257") (pin "2") (pinfunction "2_2") (pintype "passive"))
      (node (ref "C259") (pin "2") (pinfunction "2_2") (pintype "passive"))
      (node (ref "IC11") (pin "3") (pinfunction "GND_3") (pintype "passive"))
      (node (ref "IC11") (pin "4") (pinfunction "LDAC#_4") (pintype "passive"))
      (node (ref "IC13") (pin "7") (pinfunction "GND_7") (pintype "passive"))
      (node (ref "J2") (pin "2") (pinfunction "2_2") (pintype "passive"))
      (node (ref "XC4") (pin "105") (pinfunction "41_105") (pintype "passive"))
      (node (ref "XC4") (pin "106") (pinfunction "42_106") (pintype "passive"))
      (node (ref "XC4") (pin "111") (pinfunction "47_111") (pintype "passive"))
      (node (ref "XC4") (pin "112") (pinfunction "48_112") (pintype "passive"))
      (node (ref "XC4") (pin "118") (pinfunction "54_118") (pintype "passive"))
      (node (ref "XC4") (pin "122") (pinfunction "58_122") (pintype "passive"))
      (node (ref "XC4") (pin "127") (pinfunction "63_127") (pintype "passive"))
      (node (ref "XC4") (pin "128") (pinfunction "64_128") (pintype "passive"))
    )
    (net (code "82") (name "AGND_TX") (class "Default")
      (node (ref "C232") (pin "2") (pinfunction "2_2") (pintype "passive"))
      (node (ref "C234") (pin "1") (pinfunction "1_1") (pintype "passive"))
      (node (ref "C236") (pin "2") (pinfunction "2_2") (pintype "passive"))
      (node (ref "C238") (pin "1") (pinfunction "1_1") (pintype "passive"))
      (node (ref "C254") (pin "2") (pinfunction "2_2") (pintype "passive"))
      (node (ref "C256") (pin "2") (pinfunction "2_2") (pintype "passive"))
      (node (ref "C258") (pin "2") (pinfunction "2_2") (pintype "passive"))
      (node (ref "IC10") (pin "3") (pinfunction "GND_3") (pintype "passive"))
      (node (ref "IC10") (pin "4") (pinfunction "LDAC#_4") (pintype "passive"))
      (node (ref "IC12") (pin "7") (pinfunction "GND_7") (pintype "passive"))
      (node (ref "J1") (pin "2") (pinfunction "2_2") (pintype "passive"))
      (node (ref "XC4") (pin "41") (pinfunction "41_41") (pintype "passive"))
      (node (ref "XC4") (pin "42") (pinfunction "42_42") (pintype "passive"))
      (node (ref "XC4") (pin "47") (pinfunction "47_47") (pintype "passive"))
      (node (ref "XC4") (pin "48") (pinfunction "48_48") (pintype "passive"))
      (node (ref "XC4") (pin "53") (pinfunction "53_53") (pintype "passive"))
      (node (ref "XC4") (pin "57") (pinfunction "57_57") (pintype "passive"))
      (node (ref "XC4") (pin "63") (pinfunction "63_63") (pintype "passive"))
      (node (ref "XC4") (pin "64") (pinfunction "64_64") (pintype "passive"))
    )
    (net (code "83") (name "AVDD_RX") (class "Default")
      (node (ref "C233") (pin "1") (pinfunction "1_1") (pintype "passive"))
      (node (ref "C237") (pin "1") (pinfunction "1_1") (pintype "passive"))
      (node (ref "C239") (pin "1") (pinfunction "1_1") (pintype "passive"))
      (node (ref "C255") (pin "1") (pinfunction "1_1") (pintype "passive"))
      (node (ref "C257") (pin "1") (pinfunction "1_1") (pintype "passive"))
      (node (ref "C259") (pin "1") (pinfunction "1_1") (pintype "passive"))
      (node (ref "IC11") (pin "5") (pinfunction "CLR#_5") (pintype "passive"))
      (node (ref "IC11") (pin "9") (pinfunction "Vdd_9") (pintype "passive"))
      (node (ref "IC13") (pin "8") (pinfunction "Vdd_8") (pintype "passive"))
      (node (ref "L28") (pin "1") (pinfunction "1_1") (pintype "passive"))
      (node (ref "L32") (pin "2") (pinfunction "2_2") (pintype "passive"))
      (node (ref "XC4") (pin "107") (pinfunction "43_107") (pintype "passive"))
      (node (ref "XC4") (pin "108") (pinfunction "44_108") (pintype "passive"))
      (node (ref "XC4") (pin "109") (pinfunction "45_109") (pintype "passive"))
      (node (ref "XC4") (pin "110") (pinfunction "46_110") (pintype "passive"))
    )
    (net (code "84") (name "AVDD_TX") (class "Default")
      (node (ref "C232") (pin "1") (pinfunction "1_1") (pintype "passive"))
      (node (ref "C236") (pin "1") (pinfunction "1_1") (pintype "passive"))
      (node (ref "C238") (pin "2") (pinfunction "2_2") (pintype "passive"))
      (node (ref "C254") (pin "1") (pinfunction "1_1") (pintype "passive"))
      (node (ref "C256") (pin "1") (pinfunction "1_1") (pintype "passive"))
      (node (ref "C258") (pin "1") (pinfunction "1_1") (pintype "passive"))
      (node (ref "IC10") (pin "5") (pinfunction "CLR#_5") (pintype "passive"))
      (node (ref "IC10") (pin "9") (pinfunction "Vdd_9") (pintype "passive"))
      (node (ref "IC12") (pin "8") (pinfunction "Vdd_8") (pintype "passive"))
      (node (ref "L27") (pin "1") (pinfunction "1_1") (pintype "passive"))
      (node (ref "L31") (pin "2") (pinfunction "2_2") (pintype "passive"))
      (node (ref "XC4") (pin "43") (pinfunction "43_43") (pintype "passive"))
      (node (ref "XC4") (pin "44") (pinfunction "44_44") (pintype "passive"))
      (node (ref "XC4") (pin "45") (pinfunction "45_45") (pintype "passive"))
      (node (ref "XC4") (pin "46") (pinfunction "46_46") (pintype "passive"))
    )
    (net (code "85") (name "DVDD_RX") (class "Default")
      (node (ref "C245") (pin "1") (pinfunction "1_1") (pintype "passive"))
      (node (ref "C247") (pin "1") (pinfunction "1_1") (pintype "passive"))
      (node (ref "C249") (pin "1") (pinfunction "1_1") (pintype "passive"))
      (node (ref "L30") (pin "1") (pinfunction "1_1") (pintype "passive"))
      (node (ref "XC4") (pin "71") (pinfunction "7_71") (pintype "passive"))
      (node (ref "XC4") (pin "73") (pinfunction "9_73") (pintype "passive"))
      (node (ref "XC4") (pin "85") (pinfunction "21_85") (pintype "passive"))
    )
    (net (code "86") (name "DVDD_TX") (class "Default")
      (node (ref "C244") (pin "1") (pinfunction "1_1") (pintype "passive"))
      (node (ref "C246") (pin "1") (pinfunction "1_1") (pintype "passive"))
      (node (ref "C248") (pin "1") (pinfunction "1_1") (pintype "passive"))
      (node (ref "L29") (pin "1") (pinfunction "1_1") (pintype "passive"))
      (node (ref "XC4") (pin "10") (pinfunction "10_10") (pintype "passive"))
      (node (ref "XC4") (pin "8") (pinfunction "8_8") (pintype "passive"))
    )
    (net (code "87") (name "GND") (class "Default")
      (node (ref "C222") (pin "2") (pinfunction "2_2") (pintype "passive"))
      (node (ref "C223") (pin "2") (pinfunction "2_2") (pintype "passive"))
      (node (ref "C224") (pin "2") (pinfunction "2_2") (pintype "passive"))
      (node (ref "C225") (pin "2") (pinfunction "2_2") (pintype "passive"))
      (node (ref "C226") (pin "2") (pinfunction "2_2") (pintype "passive"))
      (node (ref "C227") (pin "2") (pinfunction "2_2") (pintype "passive"))
      (node (ref "C228") (pin "2") (pinfunction "2_2") (pintype "passive"))
      (node (ref "C229") (pin "2") (pinfunction "2_2") (pintype "passive"))
      (node (ref "C230") (pin "2") (pinfunction "2_2") (pintype "passive"))
      (node (ref "C231") (pin "2") (pinfunction "2_2") (pintype "passive"))
      (node (ref "C240") (pin "2") (pinfunction "2_2") (pintype "passive"))
      (node (ref "C241") (pin "2") (pinfunction "2_2") (pintype "passive"))
      (node (ref "C242") (pin "2") (pinfunction "2_2") (pintype "passive"))
      (node (ref "C243") (pin "2") (pinfunction "2_2") (pintype "passive"))
      (node (ref "C244") (pin "2") (pinfunction "2_2") (pintype "passive"))
      (node (ref "C245") (pin "2") (pinfunction "2_2") (pintype "passive"))
      (node (ref "C246") (pin "2") (pinfunction "2_2") (pintype "passive"))
      (node (ref "C247") (pin "2") (pinfunction "2_2") (pintype "passive"))
      (node (ref "C248") (pin "2") (pinfunction "2_2") (pintype "passive"))
      (node (ref "C249") (pin "2") (pinfunction "2_2") (pintype "passive"))
      (node (ref "C250") (pin "2") (pinfunction "2_2") (pintype "passive"))
      (node (ref "C251") (pin "2") (pinfunction "2_2") (pintype "passive"))
      (node (ref "C252") (pin "2") (pinfunction "2_2") (pintype "passive"))
      (node (ref "C253") (pin "2") (pinfunction "2_2") (pintype "passive"))
      (node (ref "J1") (pin "1") (pinfunction "1_1") (pintype "passive"))
      (node (ref "J2") (pin "1") (pinfunction "1_1") (pintype "passive"))
      (node (ref "XC4") (pin "0") (pinfunction "M_0") (pintype "passive"))
      (node (ref "XC4") (pin "1") (pinfunction "1_1") (pintype "passive"))
      (node (ref "XC4") (pin "101") (pinfunction "37_101") (pintype "passive"))
      (node (ref "XC4") (pin "102") (pinfunction "38_102") (pintype "passive"))
      (node (ref "XC4") (pin "2") (pinfunction "2_2") (pintype "passive"))
      (node (ref "XC4") (pin "20") (pinfunction "20_20") (pintype "passive"))
      (node (ref "XC4") (pin "22") (pinfunction "22_22") (pintype "passive"))
      (node (ref "XC4") (pin "3") (pinfunction "3_3") (pintype "passive"))
      (node (ref "XC4") (pin "37") (pinfunction "37_37") (pintype "passive"))
      (node (ref "XC4") (pin "38") (pinfunction "38_38") (pintype "passive"))
      (node (ref "XC4") (pin "65") (pinfunction "1_65") (pintype "passive"))
      (node (ref "XC4") (pin "66") (pinfunction "2_66") (pintype "passive"))
      (node (ref "XC4") (pin "68") (pinfunction "4_68") (pintype "passive"))
      (node (ref "XC4") (pin "83") (pinfunction "19_83") (pintype "passive"))
    )
    (net (code "88") (name "Net-(IC10-Vref)") (class "Default")
      (node (ref "C234") (pin "2") (pinfunction "2_2") (pintype "passive"))
      (node (ref "IC10") (pin "10") (pinfunction "Vref_10") (pintype "passive"))
      (node (ref "L27") (pin "2") (pinfunction "2_2") (pintype "passive"))
    )
    (net (code "89") (name "Net-(IC11-Vref)") (class "Default")
      (node (ref "C235") (pin "2") (pinfunction "2_2") (pintype "passive"))
      (node (ref "IC11") (pin "10") (pinfunction "Vref_10") (pintype "passive"))
      (node (ref "L28") (pin "2") (pinfunction "2_2") (pintype "passive"))
    )
    (net (code "90") (name "unconnected-(FPGA1B-IO_L3N_T0_DQS_16-PadF19)") (class "Default")
      (node (ref "FPGA1") (pin "F19") (pinfunction "IO_L3N_T0_DQS_16_F19") (pintype "bidirectional"))
    )
    (net (code "91") (name "unconnected-(FPGA1B-IO_L5N_T0_16-PadF20)") (class "Default")
      (node (ref "FPGA1") (pin "F20") (pinfunction "IO_L5N_T0_16_F20") (pintype "bidirectional"))
    )
    (net (code "92") (name "unconnected-(FPGA1B-IO_L5P_T0_16-PadG19)") (class "Default")
      (node (ref "FPGA1") (pin "G19") (pinfunction "IO_L5P_T0_16_G19") (pintype "bidirectional"))
    )
    (net (code "93") (name "unconnected-(XC4-Pad24)") (class "Default")
      (node (ref "XC4") (pin "24") (pinfunction "24_24") (pintype "passive"))
    )
    (net (code "94") (name "unconnected-(XC4-Pad26)") (class "Default")
      (node (ref "XC4") (pin "26") (pinfunction "26_26") (pintype "passive"))
    )
    (net (code "95") (name "unconnected-(XC4-Pad28)") (class "Default")
      (node (ref "XC4") (pin "28") (pinfunction "28_28") (pintype "passive"))
    )
    (net (code "96") (name "unconnected-(XC4-Pad39)") (class "Default")
      (node (ref "XC4") (pin "39") (pinfunction "39_39") (pintype "passive"))
    )
    (net (code "97") (name "unconnected-(XC4-Pad40)") (class "Default")
      (node (ref "XC4") (pin "40") (pinfunction "40_40") (pintype "passive"))
    )
    (net (code "98") (name "unconnected-(XC4-Pad55)") (class "Default")
      (node (ref "XC4") (pin "55") (pinfunction "55_55") (pintype "passive"))
    )
    (net (code "99") (name "unconnected-(XC4-Pad58)") (class "Default")
      (node (ref "XC4") (pin "58") (pinfunction "58_58") (pintype "passive"))
    )
    (net (code "100") (name "unconnected-(XC4B-23-Pad87)") (class "Default")
      (node (ref "XC4") (pin "87") (pinfunction "23_87") (pintype "passive"))
    )
    (net (code "101") (name "unconnected-(XC4B-25-Pad89)") (class "Default")
      (node (ref "XC4") (pin "89") (pinfunction "25_89") (pintype "passive"))
    )
    (net (code "102") (name "unconnected-(XC4B-27-Pad91)") (class "Default")
      (node (ref "XC4") (pin "91") (pinfunction "27_91") (pintype "passive"))
    )
    (net (code "103") (name "unconnected-(XC4B-39-Pad103)") (class "Default")
      (node (ref "XC4") (pin "103") (pinfunction "39_103") (pintype "passive"))
    )
    (net (code "104") (name "unconnected-(XC4B-40-Pad104)") (class "Default")
      (node (ref "XC4") (pin "104") (pinfunction "40_104") (pintype "passive"))
    )
    (net (code "105") (name "unconnected-(XC4B-56-Pad120)") (class "Default")
      (node (ref "XC4") (pin "120") (pinfunction "56_120") (pintype "passive"))
    )
    (net (code "106") (name "unconnected-(XC4B-57-Pad121)") (class "Default")
      (node (ref "XC4") (pin "121") (pinfunction "57_121") (pintype "passive"))
    )
  )
)
